# M3SAnalyzerSniffer.net
KiCad netlist of a schematic drawn in EAGLE
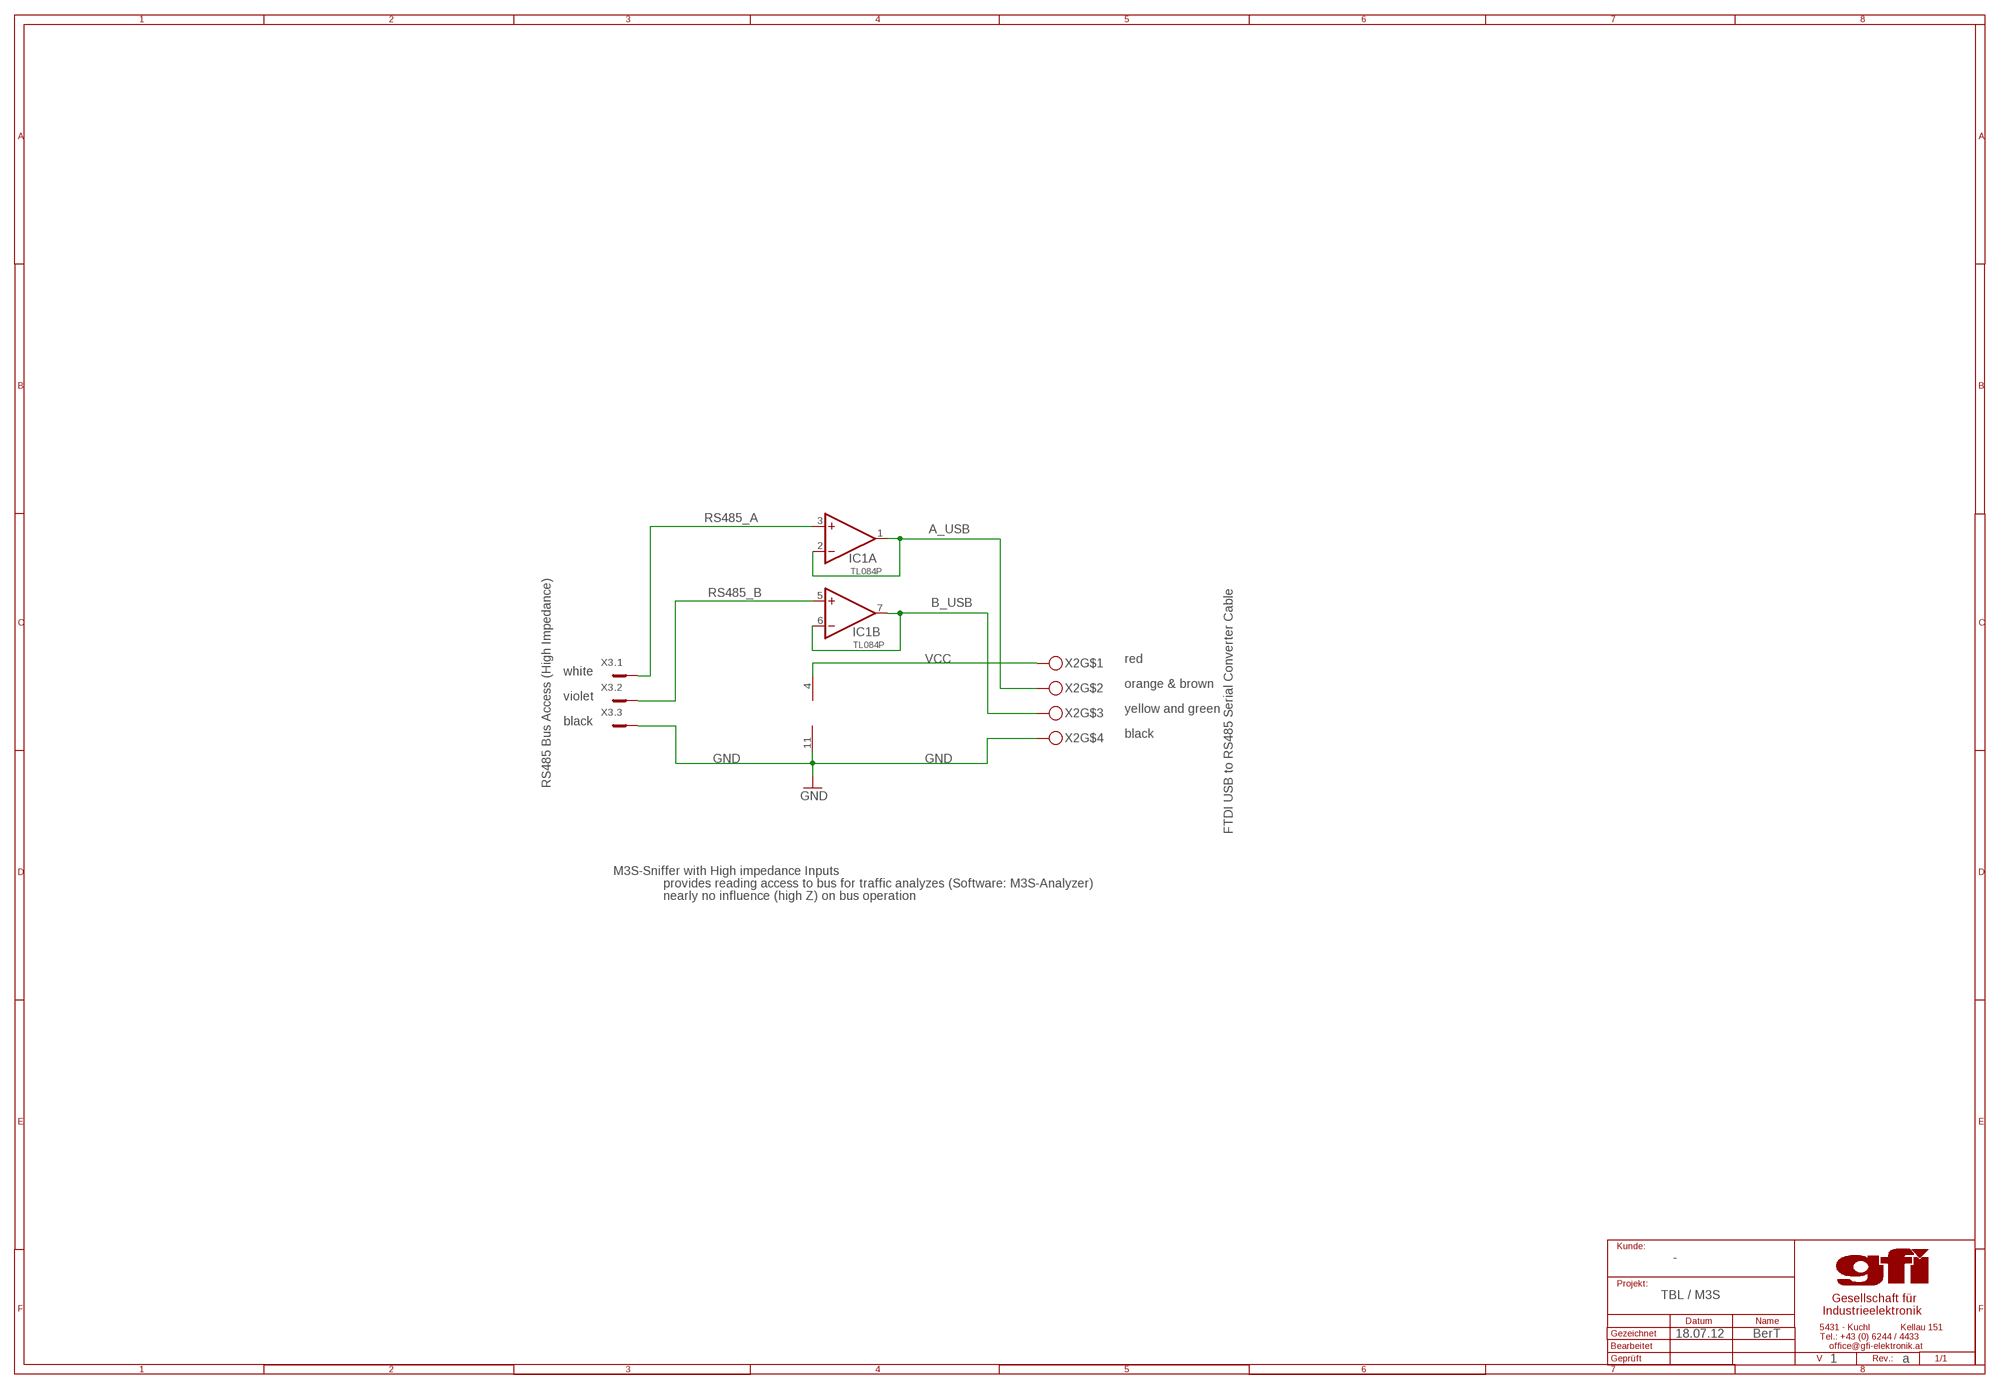
[diagram p0: schematic, sheet 1]

(export (version "E")
  (design (tool "Eeschema 10.0.6"))
  (components
    (comp (ref "IC1")
      (value "TL084P")
      (footprint "eagle-import:DIL14")
      (libsource (lib "eagle-import") (part "TL084P"))
    )
    (comp (ref "X2")
      (value "MCB1,5-2-G-3,81")
      (footprint "eagle-import:1803442")
      (libsource (lib "eagle-import") (part "MCB1,5-2-G-3,81"))
    )
    (comp (ref "X3")
      (value "MC3")
      (footprint "eagle-import:MC3")
      (libsource (lib "eagle-import") (part "MC3"))
    )
  )
  (nets
    (net (code "1") (name "/A_USB") (class "Default")
      (node (ref "IC1") (pin "1") (pinfunction "OUT_1") (pintype "output"))
      (node (ref "IC1") (pin "2") (pinfunction "-IN_2") (pintype "input"))
      (node (ref "X2") (pin "2") (pinfunction "KL_2") (pintype "passive"))
    )
    (net (code "2") (name "/B_USB") (class "Default")
      (node (ref "IC1") (pin "6") (pinfunction "-IN_6") (pintype "input"))
      (node (ref "IC1") (pin "7") (pinfunction "OUT_7") (pintype "output"))
      (node (ref "X2") (pin "3") (pinfunction "KL_3") (pintype "passive"))
    )
    (net (code "3") (name "/RS485_A") (class "Default")
      (node (ref "IC1") (pin "3") (pinfunction "+IN_3") (pintype "input"))
      (node (ref "X3") (pin "1") (pinfunction "SK_1") (pintype "passive"))
    )
    (net (code "4") (name "/RS485_B") (class "Default")
      (node (ref "IC1") (pin "5") (pinfunction "+IN_5") (pintype "input"))
      (node (ref "X3") (pin "2") (pinfunction "SK_2") (pintype "passive"))
    )
    (net (code "5") (name "/VCC") (class "Default")
      (node (ref "IC1") (pin "4") (pinfunction "V+_4") (pintype "power_in"))
      (node (ref "X2") (pin "1") (pinfunction "KL_1") (pintype "passive"))
    )
    (net (code "6") (name "GND") (class "Default")
      (node (ref "IC1") (pin "11") (pinfunction "V-_11") (pintype "power_in"))
      (node (ref "X2") (pin "4") (pinfunction "KL_4") (pintype "passive"))
      (node (ref "X3") (pin "3") (pinfunction "SK_3") (pintype "passive"))
    )
  )
)
